# 11-GPS_WIFI.net
KiCad netlist of a schematic drawn in Altium Designer
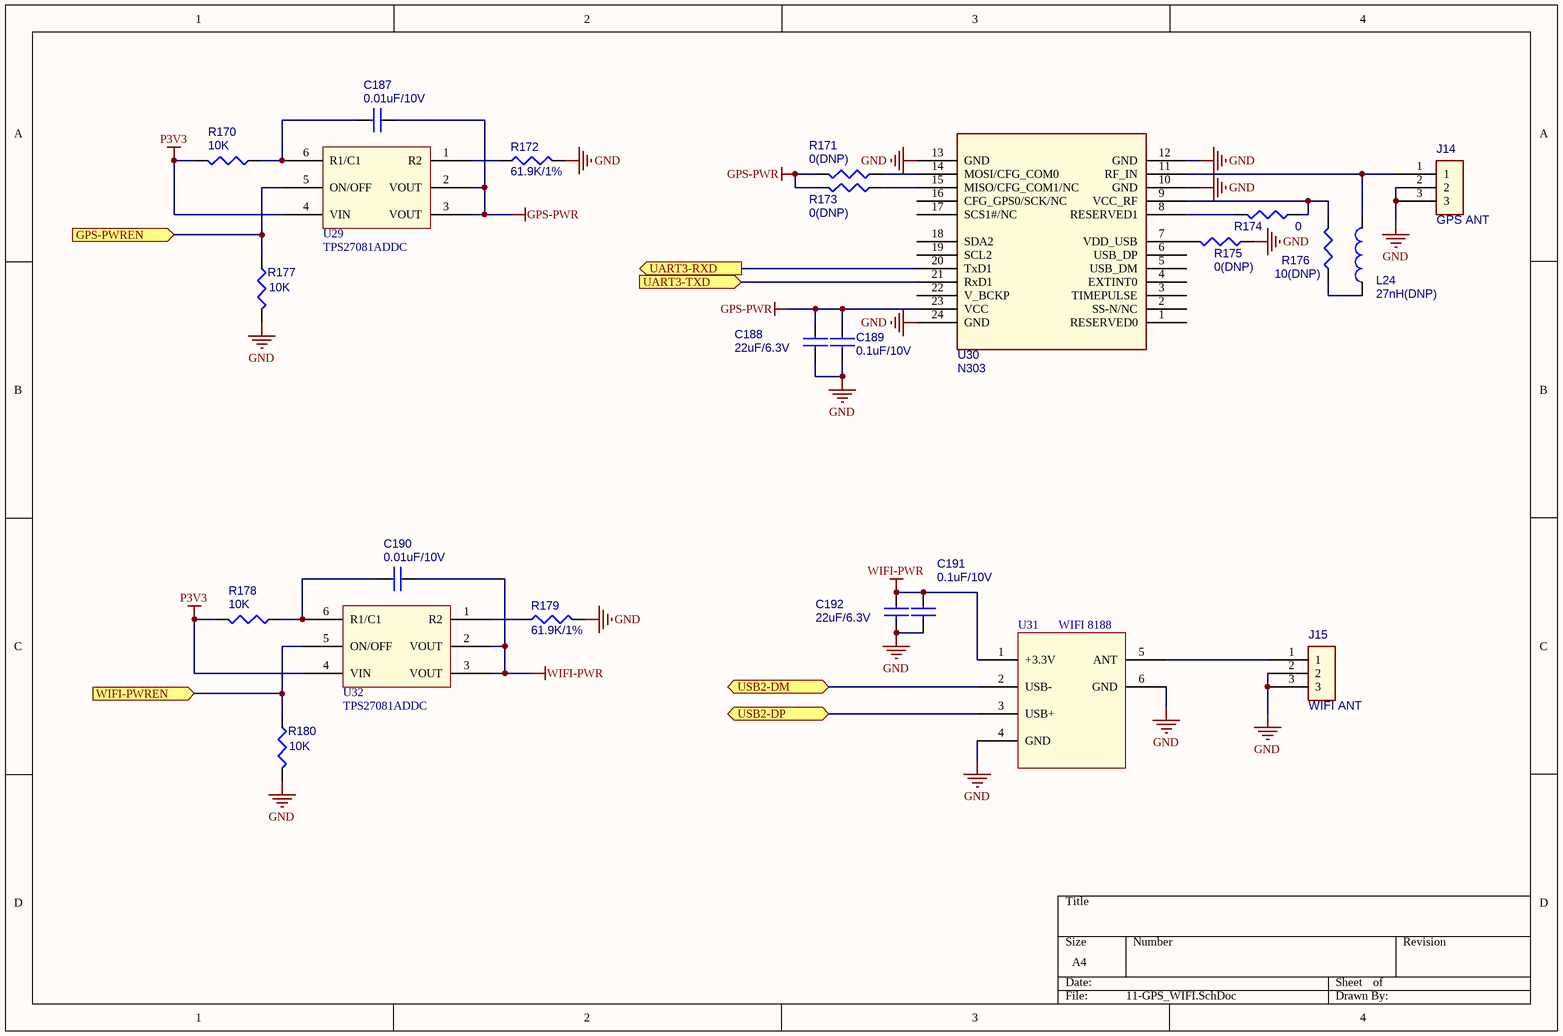
[diagram p0: 11-GPS_WIFI.SchDoc]

(export (version "E")
  (design (tool "Eeschema 10.0.6"))
  (components
    (comp (ref "C187") (value "0.01uF/10V") (footprint "0402") (libsource (lib "*") (part "P_CAP NP")))
    (comp (ref "C188") (value "22uF/6.3V") (libsource (lib "*") (part "P_CAP NP")))
    (comp (ref "C189") (value "0.1uF/10V") (libsource (lib "*") (part "P_CAP NP")))
    (comp (ref "C190") (value "0.01uF/10V") (footprint "0402") (libsource (lib "*") (part "P_CAP NP")))
    (comp (ref "C191") (value "0.1uF/10V") (libsource (lib "*") (part "P_CAP NP")))
    (comp (ref "C192") (value "22uF/6.3V") (libsource (lib "*") (part "P_CAP NP")))
    (comp (ref "J14") (value "GPS ANT") (footprint "ANT") (libsource (lib "*") (part "HRS_U_0.FL-R-SMT-10")))
    (comp (ref "J15") (value "WIFI ANT") (footprint "ANT") (libsource (lib "*") (part "HRS_U_0.FL-R-SMT-10")))
    (comp (ref "L24")
      (value "27nH(DNP)")
      (footprint "0603")
      (libsource (lib "*") (part "2.2UH_LPS3015-222MLC_1.5A_20%~D"))
    )
    (comp (ref "R170") (value "10K") (footprint "0402") (libsource (lib "*") (part "P_R")))
    (comp (ref "R171") (value "0(DNP)") (footprint "0402") (libsource (lib "*") (part "P_R")))
    (comp (ref "R172") (value "61.9K/1%") (footprint "0402") (libsource (lib "*") (part "P_R")))
    (comp (ref "R173") (value "0(DNP)") (footprint "0402") (libsource (lib "*") (part "P_R")))
    (comp (ref "R174") (value "0") (footprint "0402") (libsource (lib "*") (part "P_R")))
    (comp (ref "R175") (value "0(DNP)") (footprint "0402") (libsource (lib "*") (part "P_R")))
    (comp (ref "R176") (value "10(DNP)") (footprint "0402") (libsource (lib "*") (part "P_R")))
    (comp (ref "R177") (value "10K") (footprint "0402") (libsource (lib "*") (part "P_R")))
    (comp (ref "R178") (value "10K") (footprint "0402") (libsource (lib "*") (part "P_R")))
    (comp (ref "R179") (value "61.9K/1%") (footprint "0402") (libsource (lib "*") (part "P_R")))
    (comp (ref "R180") (value "10K") (footprint "0402") (libsource (lib "*") (part "P_R")))
    (comp (ref "U29")
      (value "TPS27081ADDC")
      (footprint "SOT23-6")
      (libsource (lib "Schlib") (part "TPS27081A"))
    )
    (comp (ref "U30") (value "N303") (footprint "NEO-6") (libsource (lib "*") (part "NEO-5M")))
    (comp (ref "U31")
      (value "WIFI 8188")
      (footprint "WIFI8188")
      (libsource (lib "Schlib") (part "WIFI 8188"))
    )
    (comp (ref "U32")
      (value "TPS27081ADDC")
      (footprint "SOT23-6")
      (libsource (lib "Schlib") (part "TPS27081A"))
    )
  )
  (nets
    (net (code "1") (name "/GPS-PWREN") (class "Default")
      (node (ref "R177") (pin "2") (pinfunction "2_2") (pintype "passive"))
      (node (ref "U29") (pin "5") (pinfunction "ON/OFF_5") (pintype "passive"))
    )
    (net (code "2") (name "/UART3-RXD") (class "Default")
      (node (ref "U30") (pin "20") (pinfunction "TxD1_20") (pintype "passive"))
    )
    (net (code "3") (name "/UART3-TXD") (class "Default")
      (node (ref "U30") (pin "21") (pinfunction "RxD1_21") (pintype "passive"))
    )
    (net (code "4") (name "/USB2-DM") (class "Default")
      (node (ref "U31") (pin "2") (pinfunction "USB-_2") (pintype "passive"))
    )
    (net (code "5") (name "/USB2-DP") (class "Default")
      (node (ref "U31") (pin "3") (pinfunction "USB+_3") (pintype "passive"))
    )
    (net (code "6") (name "/WIFI-PWREN") (class "Default")
      (node (ref "R180") (pin "2") (pinfunction "2_2") (pintype "passive"))
      (node (ref "U32") (pin "5") (pinfunction "ON/OFF_5") (pintype "passive"))
    )
    (net (code "7") (name "GND") (class "Default")
      (node (ref "C188") (pin "2") (pinfunction "2_2") (pintype "passive"))
      (node (ref "C189") (pin "2") (pinfunction "2_2") (pintype "passive"))
      (node (ref "C191") (pin "2") (pinfunction "2_2") (pintype "passive"))
      (node (ref "C192") (pin "2") (pinfunction "2_2") (pintype "passive"))
      (node (ref "J14") (pin "2") (pinfunction "2_2") (pintype "passive"))
      (node (ref "J14") (pin "3") (pinfunction "3_3") (pintype "passive"))
      (node (ref "J15") (pin "2") (pinfunction "2_2") (pintype "passive"))
      (node (ref "J15") (pin "3") (pinfunction "3_3") (pintype "passive"))
      (node (ref "R172") (pin "1") (pinfunction "1_1") (pintype "passive"))
      (node (ref "R175") (pin "1") (pinfunction "1_1") (pintype "passive"))
      (node (ref "R177") (pin "1") (pinfunction "1_1") (pintype "passive"))
      (node (ref "R179") (pin "1") (pinfunction "1_1") (pintype "passive"))
      (node (ref "R180") (pin "1") (pinfunction "1_1") (pintype "passive"))
      (node (ref "U30") (pin "10") (pinfunction "GND_10") (pintype "power_in"))
      (node (ref "U30") (pin "12") (pinfunction "GND_12") (pintype "power_in"))
      (node (ref "U30") (pin "13") (pinfunction "GND_13") (pintype "power_in"))
      (node (ref "U30") (pin "24") (pinfunction "GND_24") (pintype "power_in"))
      (node (ref "U31") (pin "4") (pinfunction "GND_4") (pintype "passive"))
      (node (ref "U31") (pin "6") (pinfunction "GND_6") (pintype "passive"))
    )
    (net (code "8") (name "GPS-PWR") (class "Default")
      (node (ref "C187") (pin "1") (pinfunction "1_1") (pintype "passive"))
      (node (ref "C188") (pin "1") (pinfunction "1_1") (pintype "passive"))
      (node (ref "C189") (pin "1") (pinfunction "1_1") (pintype "passive"))
      (node (ref "R171") (pin "2") (pinfunction "2_2") (pintype "passive"))
      (node (ref "R173") (pin "2") (pinfunction "2_2") (pintype "passive"))
      (node (ref "U29") (pin "2") (pinfunction "VOUT_2") (pintype "passive"))
      (node (ref "U29") (pin "3") (pinfunction "VOUT_3") (pintype "passive"))
      (node (ref "U30") (pin "23") (pinfunction "VCC_23") (pintype "passive"))
    )
    (net (code "9") (name "Net-(L24-Pad1)") (class "Default")
      (node (ref "L24") (pin "1") (pinfunction "1_1") (pintype "passive"))
      (node (ref "R176") (pin "1") (pinfunction "1_1") (pintype "passive"))
    )
    (net (code "10") (name "Net-(U29-R1{slash}C1)") (class "Default")
      (node (ref "C187") (pin "2") (pinfunction "2_2") (pintype "passive"))
      (node (ref "R170") (pin "2") (pinfunction "2_2") (pintype "passive"))
      (node (ref "U29") (pin "6") (pinfunction "R1/C1_6") (pintype "passive"))
    )
    (net (code "11") (name "Net-(U29-R2)") (class "Default")
      (node (ref "R172") (pin "2") (pinfunction "2_2") (pintype "passive"))
      (node (ref "U29") (pin "1") (pinfunction "R2_1") (pintype "passive"))
    )
    (net (code "12") (name "Net-(U30-MISO{slash}CFG_COM1{slash}NC)") (class "Default")
      (node (ref "R173") (pin "1") (pinfunction "1_1") (pintype "passive"))
      (node (ref "U30") (pin "15") (pinfunction "MISO/CFG_COM1/NC_15") (pintype "passive"))
    )
    (net (code "13") (name "Net-(U30-MOSI{slash}CFG_COM0)") (class "Default")
      (node (ref "R171") (pin "1") (pinfunction "1_1") (pintype "passive"))
      (node (ref "U30") (pin "14") (pinfunction "MOSI/CFG_COM0_14") (pintype "passive"))
    )
    (net (code "14") (name "Net-(U30-RESERVED1)") (class "Default")
      (node (ref "R174") (pin "2") (pinfunction "2_2") (pintype "passive"))
      (node (ref "U30") (pin "8") (pinfunction "RESERVED1_8") (pintype "passive"))
    )
    (net (code "15") (name "Net-(U30-RF_IN)") (class "Default")
      (node (ref "J14") (pin "1") (pinfunction "1_1") (pintype "passive"))
      (node (ref "L24") (pin "2") (pinfunction "2_2") (pintype "passive"))
      (node (ref "U30") (pin "11") (pinfunction "RF_IN_11") (pintype "passive"))
    )
    (net (code "16") (name "Net-(U30-VCC_RF)") (class "Default")
      (node (ref "R174") (pin "1") (pinfunction "1_1") (pintype "passive"))
      (node (ref "R176") (pin "2") (pinfunction "2_2") (pintype "passive"))
      (node (ref "U30") (pin "9") (pinfunction "VCC_RF_9") (pintype "passive"))
    )
    (net (code "17") (name "Net-(U30-VDD_USB)") (class "Default")
      (node (ref "R175") (pin "2") (pinfunction "2_2") (pintype "passive"))
      (node (ref "U30") (pin "7") (pinfunction "VDD_USB_7") (pintype "passive"))
    )
    (net (code "18") (name "Net-(U31-ANT)") (class "Default")
      (node (ref "J15") (pin "1") (pinfunction "1_1") (pintype "passive"))
      (node (ref "U31") (pin "5") (pinfunction "ANT_5") (pintype "passive"))
    )
    (net (code "19") (name "Net-(U32-R1{slash}C1)") (class "Default")
      (node (ref "C190") (pin "2") (pinfunction "2_2") (pintype "passive"))
      (node (ref "R178") (pin "2") (pinfunction "2_2") (pintype "passive"))
      (node (ref "U32") (pin "6") (pinfunction "R1/C1_6") (pintype "passive"))
    )
    (net (code "20") (name "Net-(U32-R2)") (class "Default")
      (node (ref "R179") (pin "2") (pinfunction "2_2") (pintype "passive"))
      (node (ref "U32") (pin "1") (pinfunction "R2_1") (pintype "passive"))
    )
    (net (code "21") (name "P3V3") (class "Default")
      (node (ref "R170") (pin "1") (pinfunction "1_1") (pintype "passive"))
      (node (ref "R178") (pin "1") (pinfunction "1_1") (pintype "passive"))
      (node (ref "U29") (pin "4") (pinfunction "VIN_4") (pintype "passive"))
      (node (ref "U32") (pin "4") (pinfunction "VIN_4") (pintype "passive"))
    )
    (net (code "22") (name "WIFI-PWR") (class "Default")
      (node (ref "C190") (pin "1") (pinfunction "1_1") (pintype "passive"))
      (node (ref "C191") (pin "1") (pinfunction "1_1") (pintype "passive"))
      (node (ref "C192") (pin "1") (pinfunction "1_1") (pintype "passive"))
      (node (ref "U31") (pin "1") (pinfunction "+3.3V_1") (pintype "passive"))
      (node (ref "U32") (pin "2") (pinfunction "VOUT_2") (pintype "passive"))
      (node (ref "U32") (pin "3") (pinfunction "VOUT_3") (pintype "passive"))
    )
    (net (code "23") (name "unconnected-(U30-CFG_GPS0{slash}SCK{slash}NC-Pad16)") (class "Default")
      (node (ref "U30") (pin "16") (pinfunction "CFG_GPS0/SCK/NC_16") (pintype "passive"))
    )
    (net (code "24") (name "unconnected-(U30-EXTINT0-Pad4)") (class "Default")
      (node (ref "U30") (pin "4") (pinfunction "EXTINT0_4") (pintype "passive"))
    )
    (net (code "25") (name "unconnected-(U30-RESERVED0-Pad1)") (class "Default")
      (node (ref "U30") (pin "1") (pinfunction "RESERVED0_1") (pintype "passive"))
    )
    (net (code "26") (name "unconnected-(U30-SCL2-Pad19)") (class "Default")
      (node (ref "U30") (pin "19") (pinfunction "SCL2_19") (pintype "passive"))
    )
    (net (code "27") (name "unconnected-(U30-SCS1#{slash}NC-Pad17)") (class "Default")
      (node (ref "U30") (pin "17") (pinfunction "SCS1#/NC_17") (pintype "passive"))
    )
    (net (code "28") (name "unconnected-(U30-SDA2-Pad18)") (class "Default")
      (node (ref "U30") (pin "18") (pinfunction "SDA2_18") (pintype "passive"))
    )
    (net (code "29") (name "unconnected-(U30-SS-N{slash}NC-Pad2)") (class "Default")
      (node (ref "U30") (pin "2") (pinfunction "SS-N/NC_2") (pintype "passive"))
    )
    (net (code "30") (name "unconnected-(U30-TIMEPULSE-Pad3)") (class "Default")
      (node (ref "U30") (pin "3") (pinfunction "TIMEPULSE_3") (pintype "passive"))
    )
    (net (code "31") (name "unconnected-(U30-USB_DM-Pad5)") (class "Default")
      (node (ref "U30") (pin "5") (pinfunction "USB_DM_5") (pintype "passive"))
    )
    (net (code "32") (name "unconnected-(U30-USB_DP-Pad6)") (class "Default")
      (node (ref "U30") (pin "6") (pinfunction "USB_DP_6") (pintype "passive"))
    )
    (net (code "33") (name "unconnected-(U30-V_BCKP-Pad22)") (class "Default")
      (node (ref "U30") (pin "22") (pinfunction "V_BCKP_22") (pintype "passive"))
    )
  )
)
